# PG04_Schematic_Sheet2.net
KiCad netlist of a schematic drawn in Altium Designer
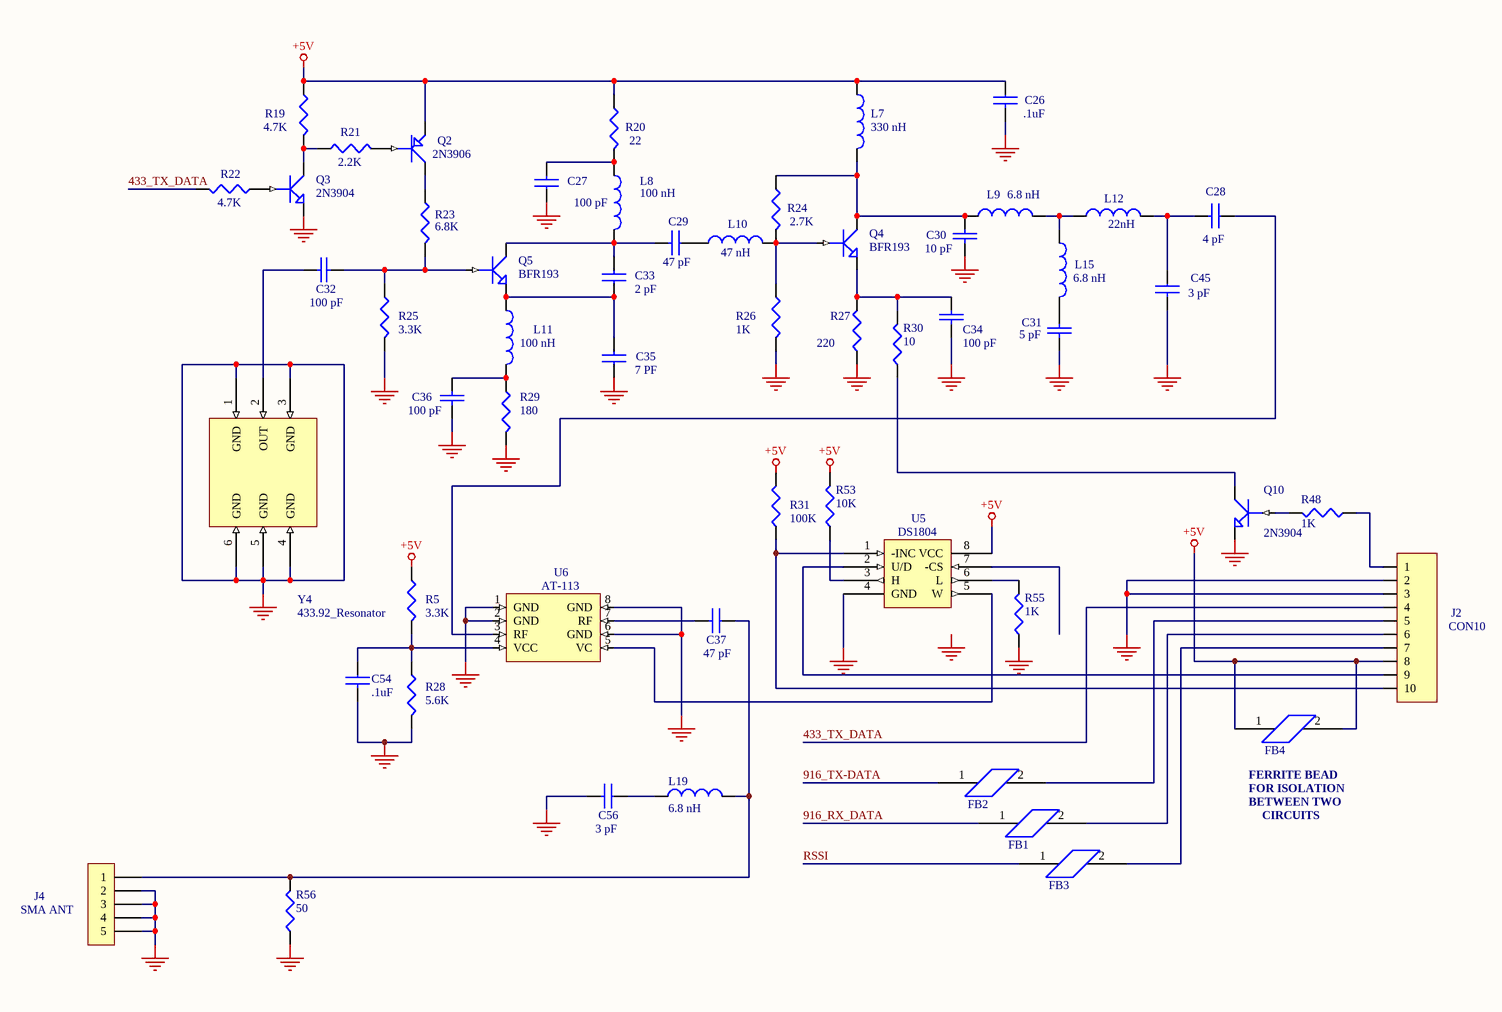
[diagram p0: PG04_Schematic Sheet2.SchDoc]

(export (version "E")
  (design (tool "Eeschema 10.0.6"))
  (components
    (comp (ref "C26") (value ".1uF") (footprint "0603") (libsource (lib "*") (part "CAP_NP")))
    (comp (ref "C27") (value "100 pF") (footprint "0603") (libsource (lib "*") (part "CAP_NP")))
    (comp (ref "C28") (value "4 pF") (footprint "0603") (libsource (lib "*") (part "CAP_NP")))
    (comp (ref "C29") (value "47 pF") (footprint "0603") (libsource (lib "*") (part "CAP_NP")))
    (comp (ref "C30")
      (value "10 pF")
      (footprint "0603")
      (description "Capacitor")
      (libsource (lib "*") (part "CAP"))
    )
    (comp (ref "C31")
      (value "5 pF")
      (footprint "0603")
      (description "Capacitor")
      (libsource (lib "*") (part "CAP"))
    )
    (comp (ref "C32")
      (value "100 pF")
      (footprint "0603")
      (description "Capacitor")
      (libsource (lib "*") (part "CAP"))
    )
    (comp (ref "C33") (value "2 pF") (footprint "0603") (libsource (lib "*") (part "CAP_NP")))
    (comp (ref "C34")
      (value "100 pF")
      (footprint "0603")
      (description "Capacitor")
      (libsource (lib "*") (part "CAP"))
    )
    (comp (ref "C35") (value "7 PF") (footprint "0603") (libsource (lib "*") (part "CAP_NP")))
    (comp (ref "C36")
      (value "100 pF")
      (footprint "0603")
      (description "Capacitor")
      (libsource (lib "*") (part "CAP"))
    )
    (comp (ref "C37") (value "47 pF") (footprint "0603") (libsource (lib "*") (part "CAP_NP")))
    (comp (ref "C45") (value "3 pF") (footprint "0603") (libsource (lib "*") (part "CAP_NP")))
    (comp (ref "C54") (value ".1uF") (footprint "0603") (libsource (lib "*") (part "CAP_NP")))
    (comp (ref "C56") (value "3 pF") (footprint "0603") (libsource (lib "*") (part "CAP_NP")))
    (comp (ref "FB1") (value "FB") (footprint "0603") (libsource (lib "*") (part "FB_0603")))
    (comp (ref "FB2") (value "FB") (footprint "0603") (libsource (lib "*") (part "FB_0603")))
    (comp (ref "FB3") (value "FB") (footprint "0603") (libsource (lib "*") (part "FB_0603")))
    (comp (ref "FB4") (value "FB") (footprint "0603") (libsource (lib "*") (part "FB_0603")))
    (comp (ref "J2") (value "CON10") (footprint "1X10 HEADER") (libsource (lib "*") (part "CON10")))
    (comp (ref "J4")
      (value "SMA ANT")
      (footprint "50 OHM ANT")
      (description "Connector")
      (libsource (lib "*") (part "CON5"))
    )
    (comp (ref "L7") (value "330 nH") (footprint "0805") (libsource (lib "*") (part "INDUCTOR")))
    (comp (ref "L8") (value "100 nH") (footprint "0603") (libsource (lib "*") (part "INDUCTOR")))
    (comp (ref "L9") (value "6.8 nH") (footprint "0603") (libsource (lib "*") (part "INDUCTOR")))
    (comp (ref "L10") (value "47 nH") (footprint "0603") (libsource (lib "*") (part "INDUCTOR")))
    (comp (ref "L11") (value "100 nH") (footprint "0603") (libsource (lib "*") (part "INDUCTOR")))
    (comp (ref "L12") (value "22nH") (footprint "0603") (libsource (lib "*") (part "INDUCTOR")))
    (comp (ref "L15") (value "6.8 nH") (footprint "0603") (libsource (lib "*") (part "INDUCTOR")))
    (comp (ref "L19") (value "6.8 nH") (footprint "0603") (libsource (lib "*") (part "INDUCTOR")))
    (comp (ref "Q2")
      (value "2N3906")
      (footprint "SOT23 TRANS")
      (description "PNP Transistor")
      (libsource (lib "*") (part "PNP1"))
    )
    (comp (ref "Q3")
      (value "2N3904")
      (footprint "SOT23 TRANS")
      (description "NPN Transistor")
      (libsource (lib "*") (part "NPN1"))
    )
    (comp (ref "Q4")
      (value "BFR193")
      (footprint "SOT23 TRANS")
      (description "NPN Transistor")
      (libsource (lib "*") (part "NPN1"))
    )
    (comp (ref "Q5")
      (value "BFR193")
      (footprint "SOT23 TRANS")
      (description "NPN Transistor")
      (libsource (lib "*") (part "NPN1"))
    )
    (comp (ref "Q10")
      (value "2N3904")
      (footprint "SOT23 TRANS")
      (description "NPN Transistor")
      (libsource (lib "*") (part "NPN1"))
    )
    (comp (ref "R5") (value "3.3K") (footprint "0603") (libsource (lib "*") (part "RESISTOR")))
    (comp (ref "R19") (value "4.7K") (footprint "0603") (libsource (lib "*") (part "RESISTOR")))
    (comp (ref "R20") (value "22") (footprint "0603") (libsource (lib "*") (part "RESISTOR")))
    (comp (ref "R21") (value "2.2K") (footprint "0603") (libsource (lib "*") (part "RESISTOR")))
    (comp (ref "R22") (value "4.7K") (footprint "0603") (libsource (lib "*") (part "RESISTOR")))
    (comp (ref "R23") (value "6.8K") (footprint "0603") (libsource (lib "*") (part "RESISTOR")))
    (comp (ref "R24") (value "2.7K") (footprint "0603") (libsource (lib "*") (part "RESISTOR")))
    (comp (ref "R25") (value "3.3K") (footprint "0603") (libsource (lib "*") (part "RESISTOR")))
    (comp (ref "R26") (value "1K") (footprint "0603") (libsource (lib "*") (part "RESISTOR")))
    (comp (ref "R27") (value "220") (footprint "0603") (libsource (lib "*") (part "RESISTOR")))
    (comp (ref "R28") (value "5.6K") (footprint "0603") (libsource (lib "*") (part "RESISTOR")))
    (comp (ref "R29") (value "180") (footprint "0603") (libsource (lib "*") (part "RESISTOR")))
    (comp (ref "R30") (value "10") (footprint "0603") (libsource (lib "*") (part "RESISTOR")))
    (comp (ref "R31") (value "100K") (footprint "0603") (libsource (lib "*") (part "RESISTOR")))
    (comp (ref "R48") (value "1K") (footprint "0603") (libsource (lib "*") (part "RESISTOR")))
    (comp (ref "R53") (value "10K") (footprint "0603") (libsource (lib "*") (part "RESISTOR")))
    (comp (ref "R55") (value "1K") (footprint "0603") (libsource (lib "*") (part "RESISTOR")))
    (comp (ref "R56") (value "50") (footprint "0603") (libsource (lib "*") (part "RESISTOR")))
    (comp (ref "U5") (value "DS1804") (footprint "SO8 SMALL") (libsource (lib "*") (part "DS1804")))
    (comp (ref "U6") (value "AT-113") (footprint "SO8") (libsource (lib "*") (part "AT-113A")))
    (comp (ref "Y4")
      (value "433.92_Resonator")
      (footprint "RESONATOR2")
      (libsource (lib "*") (part "RESONATOR2"))
    )
  )
  (nets
    (net (code "1") (name "+5V") (class "Default")
      (node (ref "C26") (pin "1") (pinfunction "1_1") (pintype "passive"))
      (node (ref "FB4") (pin "1") (pinfunction "2_1") (pintype "passive"))
      (node (ref "FB4") (pin "2") (pinfunction "1_2") (pintype "passive"))
      (node (ref "J2") (pin "8") (pinfunction "8_8") (pintype "passive"))
      (node (ref "L7") (pin "1") (pinfunction "1_1") (pintype "passive"))
      (node (ref "Q2") (pin "E") (pinfunction "E_E") (pintype "passive"))
      (node (ref "R19") (pin "1") (pinfunction "1_1") (pintype "passive"))
      (node (ref "R20") (pin "1") (pinfunction "1_1") (pintype "passive"))
      (node (ref "R31") (pin "1") (pinfunction "1_1") (pintype "passive"))
      (node (ref "R5") (pin "1") (pinfunction "1_1") (pintype "passive"))
      (node (ref "R53") (pin "2") (pinfunction "2_2") (pintype "passive"))
      (node (ref "U5") (pin "8") (pinfunction "VCC_8") (pintype "power_in"))
    )
    (net (code "2") (name "/433_TX_DATA") (class "Default")
      (node (ref "J2") (pin "4") (pinfunction "4_4") (pintype "passive"))
      (node (ref "R22") (pin "2") (pinfunction "2_2") (pintype "passive"))
    )
    (net (code "3") (name "/916_RX_DATA") (class "Default")
      (node (ref "FB1") (pin "1") (pinfunction "2_1") (pintype "passive"))
    )
    (net (code "4") (name "/916_TX-DATA") (class "Default")
      (node (ref "FB2") (pin "1") (pinfunction "2_1") (pintype "passive"))
    )
    (net (code "5") (name "/RSSI") (class "Default")
      (node (ref "FB3") (pin "1") (pinfunction "2_1") (pintype "passive"))
    )
    (net (code "6") (name "GND_SIGNAL") (class "Default")
      (node (ref "C26") (pin "2") (pinfunction "2_2") (pintype "passive"))
      (node (ref "C27") (pin "1") (pinfunction "1_1") (pintype "passive"))
      (node (ref "C30") (pin "2") (pinfunction "2_2") (pintype "passive"))
      (node (ref "C31") (pin "2") (pinfunction "2_2") (pintype "passive"))
      (node (ref "C34") (pin "2") (pinfunction "2_2") (pintype "passive"))
      (node (ref "C35") (pin "1") (pinfunction "1_1") (pintype "passive"))
      (node (ref "C36") (pin "2") (pinfunction "2_2") (pintype "passive"))
      (node (ref "C45") (pin "2") (pinfunction "2_2") (pintype "passive"))
      (node (ref "C54") (pin "2") (pinfunction "2_2") (pintype "passive"))
      (node (ref "C56") (pin "2") (pinfunction "2_2") (pintype "passive"))
      (node (ref "J2") (pin "2") (pinfunction "2_2") (pintype "passive"))
      (node (ref "J2") (pin "3") (pinfunction "3_3") (pintype "passive"))
      (node (ref "J4") (pin "2") (pinfunction "2_2") (pintype "passive"))
      (node (ref "J4") (pin "3") (pinfunction "3_3") (pintype "passive"))
      (node (ref "J4") (pin "4") (pinfunction "4_4") (pintype "passive"))
      (node (ref "J4") (pin "5") (pinfunction "5_5") (pintype "passive"))
      (node (ref "Q10") (pin "E") (pinfunction "E_E") (pintype "passive"))
      (node (ref "Q3") (pin "E") (pinfunction "E_E") (pintype "passive"))
      (node (ref "R25") (pin "2") (pinfunction "2_2") (pintype "passive"))
      (node (ref "R26") (pin "2") (pinfunction "2_2") (pintype "passive"))
      (node (ref "R27") (pin "2") (pinfunction "2_2") (pintype "passive"))
      (node (ref "R28") (pin "2") (pinfunction "2_2") (pintype "passive"))
      (node (ref "R29") (pin "2") (pinfunction "2_2") (pintype "passive"))
      (node (ref "R55") (pin "1") (pinfunction "1_1") (pintype "passive"))
      (node (ref "R56") (pin "1") (pinfunction "1_1") (pintype "passive"))
      (node (ref "U5") (pin "4") (pinfunction "GND_4") (pintype "power_in"))
      (node (ref "U6") (pin "1") (pinfunction "GND_1") (pintype "input"))
      (node (ref "U6") (pin "2") (pinfunction "GND_2") (pintype "input"))
      (node (ref "U6") (pin "6") (pinfunction "GND_6") (pintype "input"))
      (node (ref "U6") (pin "8") (pinfunction "GND_8") (pintype "input"))
      (node (ref "Y4") (pin "1") (pinfunction "GND_1") (pintype "input"))
      (node (ref "Y4") (pin "3") (pinfunction "GND_3") (pintype "input"))
      (node (ref "Y4") (pin "4") (pinfunction "GND_4") (pintype "input"))
      (node (ref "Y4") (pin "5") (pinfunction "GND_5") (pintype "input"))
      (node (ref "Y4") (pin "6") (pinfunction "GND_6") (pintype "input"))
    )
    (net (code "7") (name "Net-(C27-Pad2)") (class "Default")
      (node (ref "C27") (pin "2") (pinfunction "2_2") (pintype "passive"))
      (node (ref "L8") (pin "1") (pinfunction "1_1") (pintype "passive"))
      (node (ref "R20") (pin "2") (pinfunction "2_2") (pintype "passive"))
    )
    (net (code "8") (name "Net-(C28-Pad1)") (class "Default")
      (node (ref "C28") (pin "1") (pinfunction "1_1") (pintype "passive"))
      (node (ref "U6") (pin "3") (pinfunction "RF_3") (pintype "input"))
    )
    (net (code "9") (name "Net-(C28-Pad2)") (class "Default")
      (node (ref "C28") (pin "2") (pinfunction "2_2") (pintype "passive"))
      (node (ref "C45") (pin "1") (pinfunction "1_1") (pintype "passive"))
      (node (ref "L12") (pin "2") (pinfunction "2_2") (pintype "passive"))
    )
    (net (code "10") (name "Net-(C29-Pad1)") (class "Default")
      (node (ref "C29") (pin "1") (pinfunction "1_1") (pintype "passive"))
      (node (ref "L10") (pin "1") (pinfunction "1_1") (pintype "passive"))
    )
    (net (code "11") (name "Net-(C29-Pad2)") (class "Default")
      (node (ref "C29") (pin "2") (pinfunction "2_2") (pintype "passive"))
      (node (ref "C33") (pin "2") (pinfunction "2_2") (pintype "passive"))
      (node (ref "L8") (pin "2") (pinfunction "2_2") (pintype "passive"))
      (node (ref "Q5") (pin "C") (pinfunction "C_C") (pintype "passive"))
    )
    (net (code "12") (name "Net-(C30-Pad1)") (class "Default")
      (node (ref "C30") (pin "1") (pinfunction "1_1") (pintype "passive"))
      (node (ref "L7") (pin "2") (pinfunction "2_2") (pintype "passive"))
      (node (ref "L9") (pin "1") (pinfunction "1_1") (pintype "passive"))
      (node (ref "Q4") (pin "C") (pinfunction "C_C") (pintype "passive"))
      (node (ref "R24") (pin "1") (pinfunction "1_1") (pintype "passive"))
    )
    (net (code "13") (name "Net-(C31-Pad1)") (class "Default")
      (node (ref "C31") (pin "1") (pinfunction "1_1") (pintype "passive"))
      (node (ref "L15") (pin "2") (pinfunction "2_2") (pintype "passive"))
    )
    (net (code "14") (name "Net-(C32-Pad2)") (class "Default")
      (node (ref "C32") (pin "2") (pinfunction "2_2") (pintype "passive"))
      (node (ref "Q5") (pin "B") (pinfunction "B_B") (pintype "input"))
      (node (ref "R23") (pin "2") (pinfunction "2_2") (pintype "passive"))
      (node (ref "R25") (pin "1") (pinfunction "1_1") (pintype "passive"))
    )
    (net (code "15") (name "Net-(C33-Pad1)") (class "Default")
      (node (ref "C33") (pin "1") (pinfunction "1_1") (pintype "passive"))
      (node (ref "C35") (pin "2") (pinfunction "2_2") (pintype "passive"))
      (node (ref "L11") (pin "1") (pinfunction "1_1") (pintype "passive"))
      (node (ref "Q5") (pin "E") (pinfunction "E_E") (pintype "passive"))
    )
    (net (code "16") (name "Net-(C34-Pad1)") (class "Default")
      (node (ref "C34") (pin "1") (pinfunction "1_1") (pintype "passive"))
      (node (ref "Q4") (pin "E") (pinfunction "E_E") (pintype "passive"))
      (node (ref "R27") (pin "1") (pinfunction "1_1") (pintype "passive"))
      (node (ref "R30") (pin "2") (pinfunction "2_2") (pintype "passive"))
    )
    (net (code "17") (name "Net-(C36-Pad1)") (class "Default")
      (node (ref "C36") (pin "1") (pinfunction "1_1") (pintype "passive"))
      (node (ref "L11") (pin "2") (pinfunction "2_2") (pintype "passive"))
      (node (ref "R29") (pin "1") (pinfunction "1_1") (pintype "passive"))
    )
    (net (code "18") (name "Net-(C37-Pad1)") (class "Default")
      (node (ref "C37") (pin "1") (pinfunction "1_1") (pintype "passive"))
      (node (ref "J4") (pin "1") (pinfunction "1_1") (pintype "passive"))
      (node (ref "L19") (pin "2") (pinfunction "2_2") (pintype "passive"))
      (node (ref "R56") (pin "2") (pinfunction "2_2") (pintype "passive"))
    )
    (net (code "19") (name "Net-(C37-Pad2)") (class "Default")
      (node (ref "C37") (pin "2") (pinfunction "2_2") (pintype "passive"))
      (node (ref "U6") (pin "7") (pinfunction "RF_7") (pintype "input"))
    )
    (net (code "20") (name "Net-(C56-Pad1)") (class "Default")
      (node (ref "C56") (pin "1") (pinfunction "1_1") (pintype "passive"))
      (node (ref "L19") (pin "1") (pinfunction "1_1") (pintype "passive"))
    )
    (net (code "21") (name "Net-(FB1-1)") (class "Default")
      (node (ref "FB1") (pin "2") (pinfunction "1_2") (pintype "passive"))
      (node (ref "J2") (pin "6") (pinfunction "6_6") (pintype "passive"))
    )
    (net (code "22") (name "Net-(FB2-1)") (class "Default")
      (node (ref "FB2") (pin "2") (pinfunction "1_2") (pintype "passive"))
      (node (ref "J2") (pin "5") (pinfunction "5_5") (pintype "passive"))
    )
    (net (code "23") (name "Net-(FB3-1)") (class "Default")
      (node (ref "FB3") (pin "2") (pinfunction "1_2") (pintype "passive"))
      (node (ref "J2") (pin "7") (pinfunction "7_7") (pintype "passive"))
    )
    (net (code "24") (name "Net-(J2-Pad1)") (class "Default")
      (node (ref "J2") (pin "1") (pinfunction "1_1") (pintype "passive"))
      (node (ref "R48") (pin "2") (pinfunction "2_2") (pintype "passive"))
    )
    (net (code "25") (name "Net-(L10-Pad2)") (class "Default")
      (node (ref "L10") (pin "2") (pinfunction "2_2") (pintype "passive"))
      (node (ref "Q4") (pin "B") (pinfunction "B_B") (pintype "input"))
      (node (ref "R24") (pin "2") (pinfunction "2_2") (pintype "passive"))
      (node (ref "R26") (pin "1") (pinfunction "1_1") (pintype "passive"))
    )
    (net (code "26") (name "Net-(L12-Pad1)") (class "Default")
      (node (ref "L12") (pin "1") (pinfunction "1_1") (pintype "passive"))
      (node (ref "L15") (pin "1") (pinfunction "1_1") (pintype "passive"))
      (node (ref "L9") (pin "2") (pinfunction "2_2") (pintype "passive"))
    )
    (net (code "27") (name "Net-(Q2-PadB)") (class "Default")
      (node (ref "Q2") (pin "B") (pinfunction "B_B") (pintype "input"))
      (node (ref "R21") (pin "2") (pinfunction "2_2") (pintype "passive"))
    )
    (net (code "28") (name "Net-(Q2-PadC)") (class "Default")
      (node (ref "Q2") (pin "C") (pinfunction "C_C") (pintype "passive"))
      (node (ref "R23") (pin "1") (pinfunction "1_1") (pintype "passive"))
    )
    (net (code "29") (name "Net-(Q3-PadB)") (class "Default")
      (node (ref "Q3") (pin "B") (pinfunction "B_B") (pintype "input"))
      (node (ref "R22") (pin "1") (pinfunction "1_1") (pintype "passive"))
    )
    (net (code "30") (name "Net-(Q3-PadC)") (class "Default")
      (node (ref "Q3") (pin "C") (pinfunction "C_C") (pintype "passive"))
      (node (ref "R19") (pin "2") (pinfunction "2_2") (pintype "passive"))
      (node (ref "R21") (pin "1") (pinfunction "1_1") (pintype "passive"))
    )
    (net (code "31") (name "Net-(Q10-PadB)") (class "Default")
      (node (ref "Q10") (pin "B") (pinfunction "B_B") (pintype "input"))
      (node (ref "R48") (pin "1") (pinfunction "1_1") (pintype "passive"))
    )
    (net (code "32") (name "Net-(Q10-PadC)") (class "Default")
      (node (ref "Q10") (pin "C") (pinfunction "C_C") (pintype "passive"))
      (node (ref "R30") (pin "1") (pinfunction "1_1") (pintype "passive"))
    )
    (net (code "33") (name "Net-(U5--INC)") (class "Default")
      (node (ref "J2") (pin "10") (pinfunction "10_10") (pintype "passive"))
      (node (ref "R31") (pin "2") (pinfunction "2_2") (pintype "passive"))
      (node (ref "U5") (pin "1") (pinfunction "-INC_1") (pintype "input"))
    )
    (net (code "34") (name "Net-(U5-H)") (class "Default")
      (node (ref "R53") (pin "1") (pinfunction "1_1") (pintype "passive"))
      (node (ref "U5") (pin "3") (pinfunction "H_3") (pintype "output"))
    )
    (net (code "35") (name "Net-(U5-L)") (class "Default")
      (node (ref "R55") (pin "2") (pinfunction "2_2") (pintype "passive"))
      (node (ref "U5") (pin "6") (pinfunction "L_6") (pintype "output"))
    )
    (net (code "36") (name "Net-(U5-U{slash}D)") (class "Default")
      (node (ref "J2") (pin "9") (pinfunction "9_9") (pintype "passive"))
      (node (ref "U5") (pin "2") (pinfunction "U/D_2") (pintype "input"))
    )
    (net (code "37") (name "Net-(U5-W)") (class "Default")
      (node (ref "U5") (pin "5") (pinfunction "W_5") (pintype "output"))
      (node (ref "U6") (pin "5") (pinfunction "VC_5") (pintype "input"))
    )
    (net (code "38") (name "Net-(U6-VCC)") (class "Default")
      (node (ref "C54") (pin "1") (pinfunction "1_1") (pintype "passive"))
      (node (ref "R28") (pin "1") (pinfunction "1_1") (pintype "passive"))
      (node (ref "R5") (pin "2") (pinfunction "2_2") (pintype "passive"))
      (node (ref "U6") (pin "4") (pinfunction "VCC_4") (pintype "input"))
    )
    (net (code "39") (name "Net-(Y4-OUT)") (class "Default")
      (node (ref "C32") (pin "1") (pinfunction "1_1") (pintype "passive"))
      (node (ref "Y4") (pin "2") (pinfunction "OUT_2") (pintype "input"))
    )
    (net (code "40") (name "unconnected-(U5--CS-Pad7)") (class "Default")
      (node (ref "U5") (pin "7") (pinfunction "-CS_7") (pintype "input"))
    )
  )
)
